# ads1115_feather_4chan.net
KiCad netlist of a schematic drawn in EAGLE
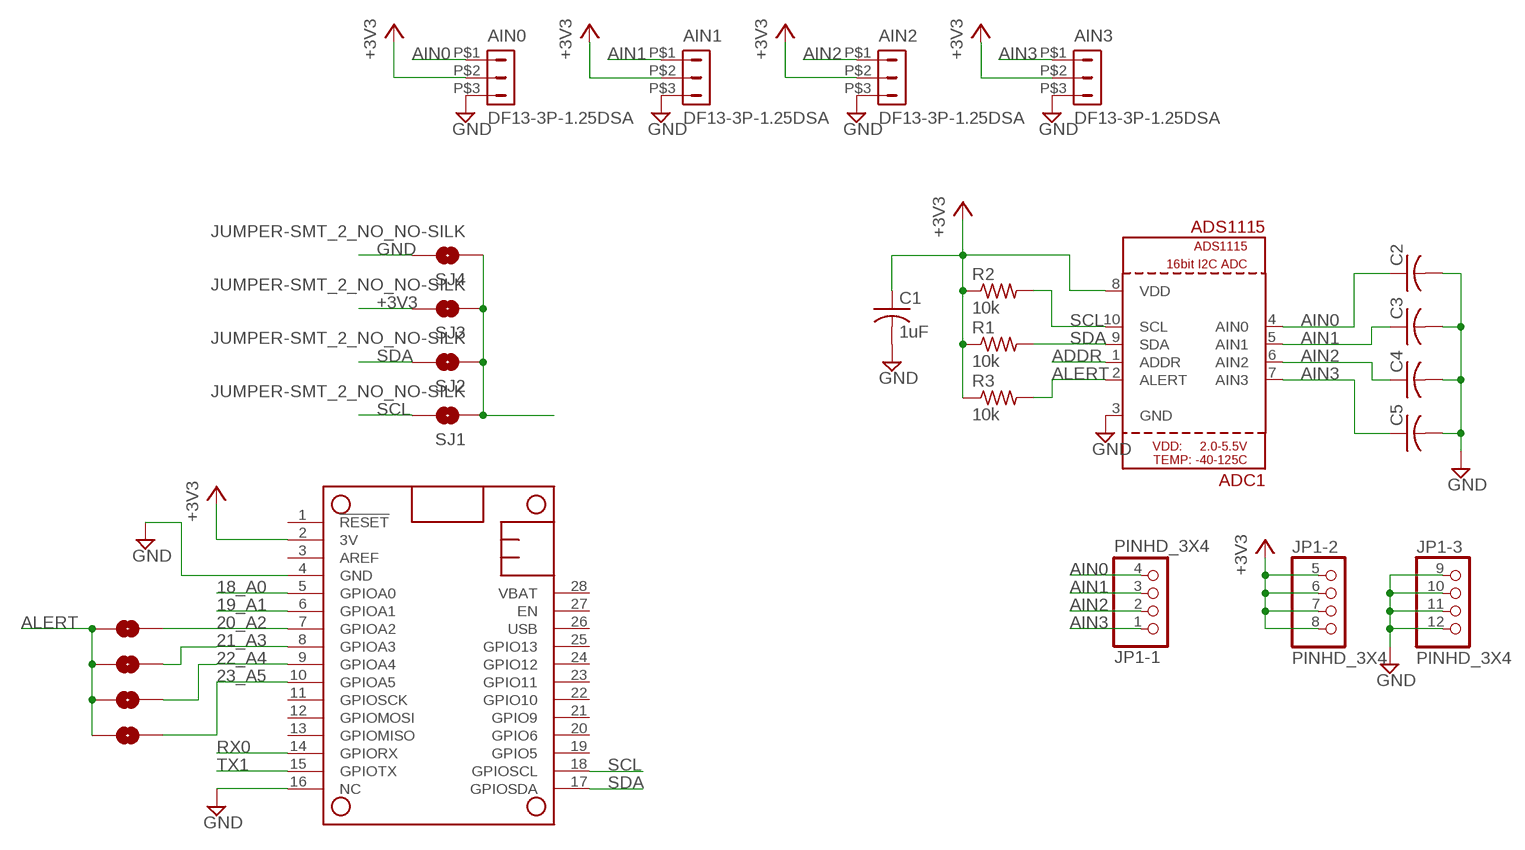
[diagram p0: schematic, sheet 1]

(export (version "E")
  (design (tool "Eeschema 10.0.6"))
  (components
    (comp (ref "ADC1")
      (value "ADS1115")
      (footprint "eagle-import:MSOP10")
      (libsource (lib "eagle-import") (part "ADS1115"))
    )
    (comp (ref "AIN0")
      (value "DF13-3P-1.25DSA")
      (footprint "eagle-import:DF13-3P-1.25DSA")
      (libsource (lib "eagle-import") (part "DF13-3P-1.25DSA"))
    )
    (comp (ref "AIN1")
      (value "DF13-3P-1.25DSA")
      (footprint "eagle-import:DF13-3P-1.25DSA")
      (libsource (lib "eagle-import") (part "DF13-3P-1.25DSA"))
    )
    (comp (ref "AIN2")
      (value "DF13-3P-1.25DSA")
      (footprint "eagle-import:DF13-3P-1.25DSA")
      (libsource (lib "eagle-import") (part "DF13-3P-1.25DSA"))
    )
    (comp (ref "AIN3")
      (value "DF13-3P-1.25DSA")
      (footprint "eagle-import:DF13-3P-1.25DSA")
      (libsource (lib "eagle-import") (part "DF13-3P-1.25DSA"))
    )
    (comp (ref "C1")
      (value "1uF")
      (footprint "eagle-import:C0805K")
      (libsource (lib "eagle-import") (part "C-USC0805K"))
    )
    (comp (ref "C2")
      (value "C-USC0805K")
      (footprint "eagle-import:C0805K")
      (libsource (lib "eagle-import") (part "C-USC0805K"))
    )
    (comp (ref "C3")
      (value "C-USC0805K")
      (footprint "eagle-import:C0805K")
      (libsource (lib "eagle-import") (part "C-USC0805K"))
    )
    (comp (ref "C4")
      (value "C-USC0805K")
      (footprint "eagle-import:C0805K")
      (libsource (lib "eagle-import") (part "C-USC0805K"))
    )
    (comp (ref "C5")
      (value "C-USC0805K")
      (footprint "eagle-import:C0805K")
      (libsource (lib "eagle-import") (part "C-USC0805K"))
    )
    (comp (ref "JP1")
      (value "PINHD_3X4")
      (footprint "eagle-import:3X4")
      (libsource (lib "eagle-import") (part "PINHD_3X4"))
    )
    (comp (ref "MS1")
      (value "FEATHERWING")
      (footprint "eagle-import:FEATHERWING")
      (libsource (lib "eagle-import") (part "FEATHERWING"))
    )
    (comp (ref "R1")
      (value "10k")
      (footprint "eagle-import:R0805")
      (libsource (lib "eagle-import") (part "R-US_R0805"))
    )
    (comp (ref "R2")
      (value "10k")
      (footprint "eagle-import:R0805")
      (libsource (lib "eagle-import") (part "R-US_R0805"))
    )
    (comp (ref "R3")
      (value "10k")
      (footprint "eagle-import:R0805")
      (libsource (lib "eagle-import") (part "R-US_R0805"))
    )
    (comp (ref "SJ1")
      (value "JUMPER-SMT_2_NO_NO-SILK")
      (footprint "eagle-import:SMT-JUMPER_2_NO_NO-SILK")
      (libsource (lib "eagle-import") (part "JUMPER-SMT_2_NO_NO-SILK"))
    )
    (comp (ref "SJ2")
      (value "JUMPER-SMT_2_NO_NO-SILK")
      (footprint "eagle-import:SMT-JUMPER_2_NO_NO-SILK")
      (libsource (lib "eagle-import") (part "JUMPER-SMT_2_NO_NO-SILK"))
    )
    (comp (ref "SJ3")
      (value "JUMPER-SMT_2_NO_NO-SILK")
      (footprint "eagle-import:SMT-JUMPER_2_NO_NO-SILK")
      (libsource (lib "eagle-import") (part "JUMPER-SMT_2_NO_NO-SILK"))
    )
    (comp (ref "SJ4")
      (value "JUMPER-SMT_2_NO_NO-SILK")
      (footprint "eagle-import:SMT-JUMPER_2_NO_NO-SILK")
      (libsource (lib "eagle-import") (part "JUMPER-SMT_2_NO_NO-SILK"))
    )
    (comp (ref "SJ5")
      (value "JUMPER-SMT_2_NO_NO-SILK")
      (footprint "eagle-import:SMT-JUMPER_2_NO_NO-SILK")
      (libsource (lib "eagle-import") (part "JUMPER-SMT_2_NO_NO-SILK"))
    )
    (comp (ref "SJ6")
      (value "JUMPER-SMT_2_NO_NO-SILK")
      (footprint "eagle-import:SMT-JUMPER_2_NO_NO-SILK")
      (libsource (lib "eagle-import") (part "JUMPER-SMT_2_NO_NO-SILK"))
    )
    (comp (ref "SJ7")
      (value "JUMPER-SMT_2_NO_NO-SILK")
      (footprint "eagle-import:SMT-JUMPER_2_NO_NO-SILK")
      (libsource (lib "eagle-import") (part "JUMPER-SMT_2_NO_NO-SILK"))
    )
    (comp (ref "SJ8")
      (value "JUMPER-SMT_2_NO_NO-SILK")
      (footprint "eagle-import:SMT-JUMPER_2_NO_NO-SILK")
      (libsource (lib "eagle-import") (part "JUMPER-SMT_2_NO_NO-SILK"))
    )
  )
  (nets
    (net (code "1") (name "+3V3") (class "Default")
      (node (ref "ADC1") (pin "8") (pinfunction "VDD_8") (pintype "bidirectional"))
      (node (ref "AIN0") (pin "P$2") (pinfunction "2_P$2") (pintype "passive"))
      (node (ref "AIN1") (pin "P$2") (pinfunction "2_P$2") (pintype "passive"))
      (node (ref "AIN2") (pin "P$2") (pinfunction "2_P$2") (pintype "passive"))
      (node (ref "AIN3") (pin "P$2") (pinfunction "2_P$2") (pintype "passive"))
      (node (ref "C1") (pin "1") (pinfunction "1_1") (pintype "passive"))
      (node (ref "JP1") (pin "5") (pinfunction "1_5") (pintype "passive"))
      (node (ref "JP1") (pin "6") (pinfunction "2_6") (pintype "passive"))
      (node (ref "JP1") (pin "7") (pinfunction "3_7") (pintype "passive"))
      (node (ref "JP1") (pin "8") (pinfunction "4_8") (pintype "passive"))
      (node (ref "MS1") (pin "2") (pinfunction "3V_2") (pintype "power_in"))
      (node (ref "R1") (pin "1") (pinfunction "1_1") (pintype "passive"))
      (node (ref "R2") (pin "1") (pinfunction "1_1") (pintype "passive"))
      (node (ref "R3") (pin "1") (pinfunction "1_1") (pintype "passive"))
      (node (ref "SJ3") (pin "2") (pinfunction "2_2") (pintype "passive"))
    )
    (net (code "2") (name "/18_A0") (class "Default")
      (node (ref "MS1") (pin "5") (pinfunction "GPIOA0_5") (pintype "bidirectional"))
    )
    (net (code "3") (name "/19_A1") (class "Default")
      (node (ref "MS1") (pin "6") (pinfunction "GPIOA1_6") (pintype "bidirectional"))
    )
    (net (code "4") (name "/20_A2") (class "Default")
      (node (ref "MS1") (pin "7") (pinfunction "GPIOA2_7") (pintype "bidirectional"))
      (node (ref "SJ7") (pin "2") (pinfunction "2_2") (pintype "passive"))
    )
    (net (code "5") (name "/21_A3") (class "Default")
      (node (ref "MS1") (pin "8") (pinfunction "GPIOA3_8") (pintype "bidirectional"))
      (node (ref "SJ6") (pin "2") (pinfunction "2_2") (pintype "passive"))
    )
    (net (code "6") (name "/22_A4") (class "Default")
      (node (ref "MS1") (pin "9") (pinfunction "GPIOA4_9") (pintype "bidirectional"))
      (node (ref "SJ5") (pin "2") (pinfunction "2_2") (pintype "passive"))
    )
    (net (code "7") (name "/23_A5") (class "Default")
      (node (ref "MS1") (pin "10") (pinfunction "GPIOA5_10") (pintype "bidirectional"))
      (node (ref "SJ8") (pin "2") (pinfunction "2_2") (pintype "passive"))
    )
    (net (code "8") (name "/ADDR") (class "Default")
      (node (ref "ADC1") (pin "1") (pinfunction "ADDR_1") (pintype "bidirectional"))
      (node (ref "SJ1") (pin "1") (pinfunction "1_1") (pintype "passive"))
      (node (ref "SJ2") (pin "1") (pinfunction "1_1") (pintype "passive"))
      (node (ref "SJ3") (pin "1") (pinfunction "1_1") (pintype "passive"))
      (node (ref "SJ4") (pin "1") (pinfunction "1_1") (pintype "passive"))
    )
    (net (code "9") (name "/AIN0") (class "Default")
      (node (ref "ADC1") (pin "4") (pinfunction "AIN0_4") (pintype "bidirectional"))
      (node (ref "AIN0") (pin "P$1") (pinfunction "1_P$1") (pintype "passive"))
      (node (ref "C2") (pin "1") (pinfunction "1_1") (pintype "passive"))
      (node (ref "JP1") (pin "4") (pinfunction "4_4") (pintype "passive"))
    )
    (net (code "10") (name "/AIN1") (class "Default")
      (node (ref "ADC1") (pin "5") (pinfunction "AIN1_5") (pintype "bidirectional"))
      (node (ref "AIN1") (pin "P$1") (pinfunction "1_P$1") (pintype "passive"))
      (node (ref "C3") (pin "1") (pinfunction "1_1") (pintype "passive"))
      (node (ref "JP1") (pin "3") (pinfunction "3_3") (pintype "passive"))
    )
    (net (code "11") (name "/AIN2") (class "Default")
      (node (ref "ADC1") (pin "6") (pinfunction "AIN2_6") (pintype "bidirectional"))
      (node (ref "AIN2") (pin "P$1") (pinfunction "1_P$1") (pintype "passive"))
      (node (ref "C4") (pin "1") (pinfunction "1_1") (pintype "passive"))
      (node (ref "JP1") (pin "2") (pinfunction "2_2") (pintype "passive"))
    )
    (net (code "12") (name "/AIN3") (class "Default")
      (node (ref "ADC1") (pin "7") (pinfunction "AIN3_7") (pintype "bidirectional"))
      (node (ref "AIN3") (pin "P$1") (pinfunction "1_P$1") (pintype "passive"))
      (node (ref "C5") (pin "1") (pinfunction "1_1") (pintype "passive"))
      (node (ref "JP1") (pin "1") (pinfunction "1_1") (pintype "passive"))
    )
    (net (code "13") (name "/ALERT") (class "Default")
      (node (ref "ADC1") (pin "2") (pinfunction "ALERT_2") (pintype "bidirectional"))
      (node (ref "R3") (pin "2") (pinfunction "2_2") (pintype "passive"))
      (node (ref "SJ5") (pin "1") (pinfunction "1_1") (pintype "passive"))
      (node (ref "SJ6") (pin "1") (pinfunction "1_1") (pintype "passive"))
      (node (ref "SJ7") (pin "1") (pinfunction "1_1") (pintype "passive"))
      (node (ref "SJ8") (pin "1") (pinfunction "1_1") (pintype "passive"))
    )
    (net (code "14") (name "/RX0") (class "Default")
      (node (ref "MS1") (pin "14") (pinfunction "GPIORX_14") (pintype "bidirectional"))
    )
    (net (code "15") (name "/SCL") (class "Default")
      (node (ref "ADC1") (pin "10") (pinfunction "SCL_10") (pintype "bidirectional"))
      (node (ref "MS1") (pin "18") (pinfunction "GPIOSCL_18") (pintype "bidirectional"))
      (node (ref "R2") (pin "2") (pinfunction "2_2") (pintype "passive"))
      (node (ref "SJ1") (pin "2") (pinfunction "2_2") (pintype "passive"))
    )
    (net (code "16") (name "/SDA") (class "Default")
      (node (ref "ADC1") (pin "9") (pinfunction "SDA_9") (pintype "bidirectional"))
      (node (ref "MS1") (pin "17") (pinfunction "GPIOSDA_17") (pintype "bidirectional"))
      (node (ref "R1") (pin "2") (pinfunction "2_2") (pintype "passive"))
      (node (ref "SJ2") (pin "2") (pinfunction "2_2") (pintype "passive"))
    )
    (net (code "17") (name "/TX1") (class "Default")
      (node (ref "MS1") (pin "15") (pinfunction "GPIOTX_15") (pintype "bidirectional"))
    )
    (net (code "18") (name "/USB") (class "Default")
      (node (ref "MS1") (pin "26") (pinfunction "USB_26") (pintype "power_in"))
    )
    (net (code "19") (name "/VBAT") (class "Default")
      (node (ref "MS1") (pin "28") (pinfunction "VBAT_28") (pintype "power_in"))
    )
    (net (code "20") (name "GND") (class "Default")
      (node (ref "ADC1") (pin "3") (pinfunction "GND_3") (pintype "bidirectional"))
      (node (ref "AIN0") (pin "P$3") (pinfunction "3_P$3") (pintype "passive"))
      (node (ref "AIN1") (pin "P$3") (pinfunction "3_P$3") (pintype "passive"))
      (node (ref "AIN2") (pin "P$3") (pinfunction "3_P$3") (pintype "passive"))
      (node (ref "AIN3") (pin "P$3") (pinfunction "3_P$3") (pintype "passive"))
      (node (ref "C1") (pin "2") (pinfunction "2_2") (pintype "passive"))
      (node (ref "C2") (pin "2") (pinfunction "2_2") (pintype "passive"))
      (node (ref "C3") (pin "2") (pinfunction "2_2") (pintype "passive"))
      (node (ref "C4") (pin "2") (pinfunction "2_2") (pintype "passive"))
      (node (ref "C5") (pin "2") (pinfunction "2_2") (pintype "passive"))
      (node (ref "JP1") (pin "10") (pinfunction "2_10") (pintype "passive"))
      (node (ref "JP1") (pin "11") (pinfunction "3_11") (pintype "passive"))
      (node (ref "JP1") (pin "12") (pinfunction "4_12") (pintype "passive"))
      (node (ref "JP1") (pin "9") (pinfunction "1_9") (pintype "passive"))
      (node (ref "MS1") (pin "16") (pinfunction "NC_16") (pintype "passive"))
      (node (ref "MS1") (pin "4") (pinfunction "GND_4") (pintype "power_in"))
      (node (ref "SJ4") (pin "2") (pinfunction "2_2") (pintype "passive"))
    )
    (net (code "21") (name "unconnected-(MS1-AREF-Pad3)") (class "Default")
      (node (ref "MS1") (pin "3") (pinfunction "AREF_3") (pintype "passive"))
    )
    (net (code "22") (name "unconnected-(MS1-EN-Pad27)") (class "Default")
      (node (ref "MS1") (pin "27") (pinfunction "EN_27") (pintype "passive"))
    )
    (net (code "23") (name "unconnected-(MS1-GPIO5-Pad19)") (class "Default")
      (node (ref "MS1") (pin "19") (pinfunction "GPIO5_19") (pintype "bidirectional"))
    )
    (net (code "24") (name "unconnected-(MS1-GPIO6-Pad20)") (class "Default")
      (node (ref "MS1") (pin "20") (pinfunction "GPIO6_20") (pintype "bidirectional"))
    )
    (net (code "25") (name "unconnected-(MS1-GPIO9-Pad21)") (class "Default")
      (node (ref "MS1") (pin "21") (pinfunction "GPIO9_21") (pintype "bidirectional"))
    )
    (net (code "26") (name "unconnected-(MS1-GPIO10-Pad22)") (class "Default")
      (node (ref "MS1") (pin "22") (pinfunction "GPIO10_22") (pintype "bidirectional"))
    )
    (net (code "27") (name "unconnected-(MS1-GPIO11-Pad23)") (class "Default")
      (node (ref "MS1") (pin "23") (pinfunction "GPIO11_23") (pintype "bidirectional"))
    )
    (net (code "28") (name "unconnected-(MS1-GPIO12-Pad24)") (class "Default")
      (node (ref "MS1") (pin "24") (pinfunction "GPIO12_24") (pintype "bidirectional"))
    )
    (net (code "29") (name "unconnected-(MS1-GPIO13-Pad25)") (class "Default")
      (node (ref "MS1") (pin "25") (pinfunction "GPIO13_25") (pintype "bidirectional"))
    )
    (net (code "30") (name "unconnected-(MS1-GPIOMISO-Pad13)") (class "Default")
      (node (ref "MS1") (pin "13") (pinfunction "GPIOMISO_13") (pintype "bidirectional"))
    )
    (net (code "31") (name "unconnected-(MS1-GPIOMOSI-Pad12)") (class "Default")
      (node (ref "MS1") (pin "12") (pinfunction "GPIOMOSI_12") (pintype "bidirectional"))
    )
    (net (code "32") (name "unconnected-(MS1-GPIOSCK-Pad11)") (class "Default")
      (node (ref "MS1") (pin "11") (pinfunction "GPIOSCK_11") (pintype "bidirectional"))
    )
    (net (code "33") (name "unconnected-(MS1-~{RESET}-Pad1)") (class "Default")
      (node (ref "MS1") (pin "1") (pinfunction "~{RESET}_1") (pintype "input"))
    )
  )
)
